# Boost_Converter.net
KiCad netlist of a schematic drawn in Altium Designer
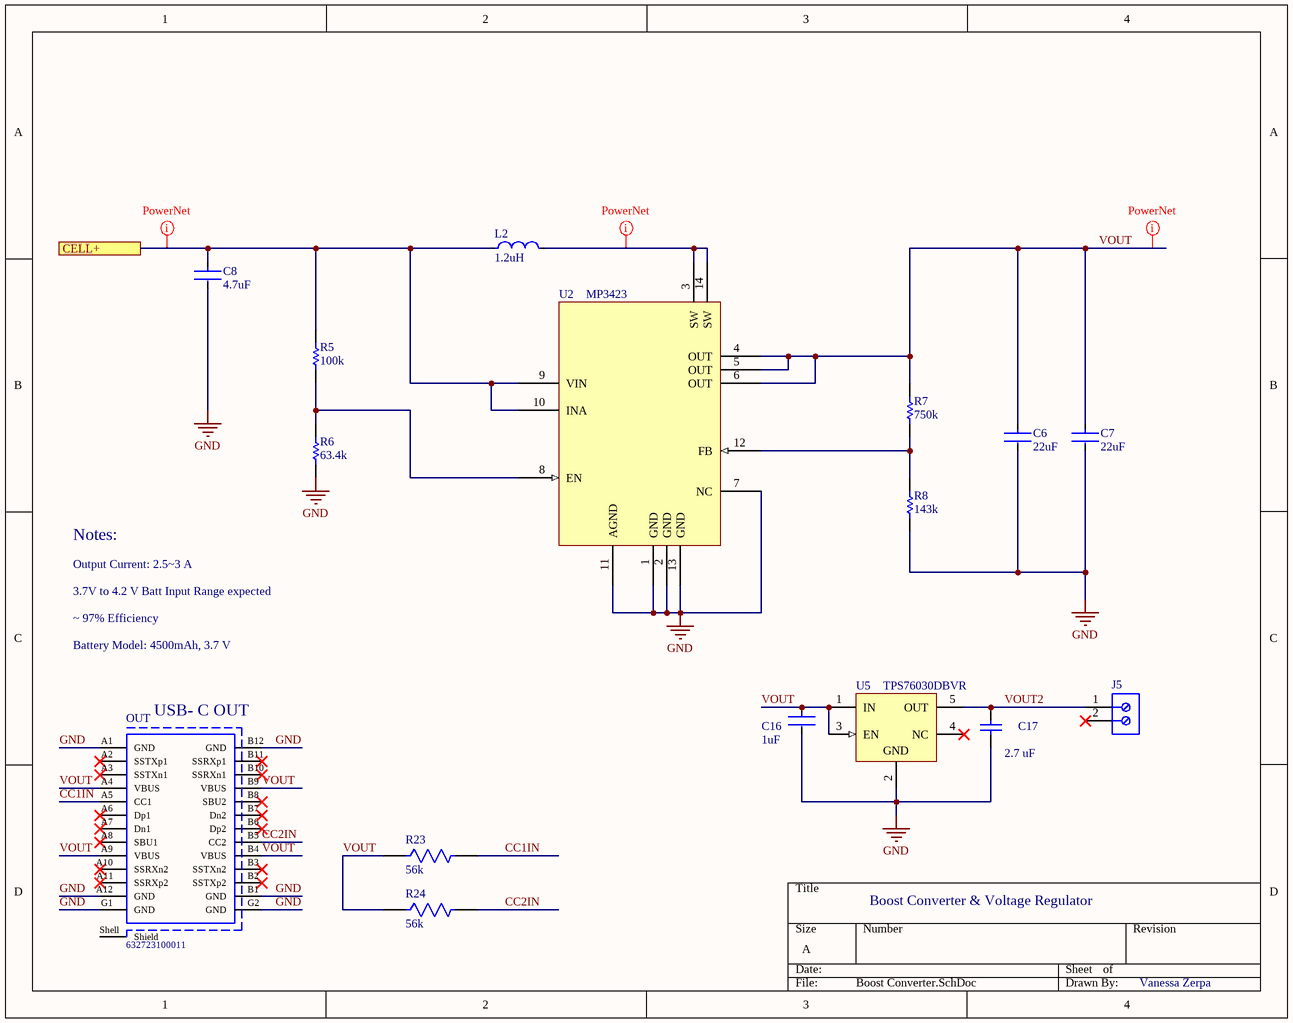
[diagram p0: Boost Converter.SchDoc]

(export (version "E")
  (design (tool "Eeschema 10.0.6"))
  (components
    (comp (ref "C6")
      (value "22uF")
      (footprint "FP-GRM21B-0_15-MFG")
      (description "Chip Multilayer Ceramic Capacitors for General Purpose, 0805, 22uF, X5R, 15%, 20%, 6.3V")
      (fields (field (name "VOLTAGE") "6.3V") (field (name "TOLERANCE") "20%"))
      (libsource (lib "Altium Content Vault") (part "b4654b650e69147ec39a6b967a45e02"))
    )
    (comp (ref "C7")
      (value "22uF")
      (footprint "FP-GRM21B-0_15-MFG")
      (description "Chip Multilayer Ceramic Capacitors for General Purpose, 0805, 22uF, X5R, 15%, 20%, 6.3V")
      (fields (field (name "VOLTAGE") "6.3V") (field (name "TOLERANCE") "20%"))
      (libsource (lib "Altium Content Vault") (part "b4654b650e69147ec39a6b967a45e02"))
    )
    (comp (ref "C8")
      (value "4.7uF")
      (footprint "FP-0805-L_2_01_0_2-W_1_25-MFG")
      (description "General Purpose Ceramic Capacitor, 0805, 4.7uF, 10%, X7R, 15%, 16V")
      (fields (field (name "VOLTAGE") "10V") (field (name "TOLERANCE") "10%"))
      (libsource (lib "Altium Content Vault") (part "02cd4be3c70576c341d710602a673aa"))
    )
    (comp (ref "C16")
      (value "1uF")
      (footprint "FP-CC0805-0_85-MFG")
      (description "CAP CER 1UF 10V X7R 0805")
      (fields
        (field (name "MANUFACTURER") "Yageo")
        (field (name "OCTOPART") "https://octopart.com/cc0805kkx7r6bb105-yageo-42522859")
      )
      (libsource (lib "Altium Content Vault") (part "11868f565c42a9108669ba33697ecf6"))
    )
    (comp (ref "C17")
      (value "2.7 uF")
      (footprint "CAPC2013X145X50LL20T25")
      (fields (field (name "PART NUMBER") "C0805C275K8PACTU") (field (name "MANUFACTURER") "Kemet"))
      (libsource (lib "Altium Content Vault") (part "CAP"))
    )
    (comp (ref "J5")
      (value "691101710002")
      (footprint "691101710002")
      (description "Series 101 - 5.00 mm Horizontal Entry Modular with Pressure Clamp WR-TBL, 2 pin")
      (fields (field (name "MANUFACTURER") "Wurth Elektronik") (field (name "PUBLISHER") "WurthElektronik"))
      (libsource (lib "Altium Content Vault") (part "WE-CN-1P-F-TB2"))
    )
    (comp (ref "L2")
      (value "1.2uH")
      (footprint "FP-LQW21HN_00-MFG")
      (description "Wire Wound Ferrite type RF Inuctor 1.2uH ±5% 100mA 3.12Ω 0805 (2012)")
      (fields (field (name "TOLERANCE") "5%"))
      (libsource (lib "Altium Content Vault") (part "725321dda6339637d4d059423bc1c3c"))
    )
    (comp (ref "OUT")
      (value "632723100011")
      (footprint "632723100011")
      (description "USB 3.1 Type C Receptacle WR-COM, Horizontal, SMT / THT")
      (fields (field (name "MANUFACTURER") "Wurth Elektronik") (field (name "PUBLISHER") "WurthElektronik"))
      (libsource (lib "Altium Content Vault") (part "WE-632723X00011"))
    )
    (comp (ref "R5")
      (value "100k")
      (footprint "RESC2013X60X35ML10T20")
      (description "Chip Resistor, 100 KOhm, +/- 1%, 0.125 W, -55 to 155 degC, 0805 (2012 Metric), RoHS, Tape and Reel")
      (fields (field (name "MANUFACTURER") "Yageo") (field (name "TOLERANCE") "1%"))
      (libsource (lib "Altium Content Vault") (part "RES-2"))
    )
    (comp (ref "R6")
      (value "63.4k")
      (footprint "RESC2013X50X30LL20T20")
      (fields (field (name "PART NUMBER") "CRCW080563K4FKEA") (field (name "MANUFACTURER") "Vishay Dale"))
      (libsource (lib "Altium Content Vault") (part "RES"))
    )
    (comp (ref "R7")
      (value "750k")
      (footprint "RESC2013X50X30LL20T20")
      (fields (field (name "MANUFACTURER") "Vishay Dale") (field (name "PART NUMBER") "CRCW0805750KFKEA"))
      (libsource (lib "Altium Content Vault") (part "RES"))
    )
    (comp (ref "R8")
      (value "143k")
      (footprint "RESC2013X70X40LL20T20")
      (fields (field (name "MANUFACTURER") "Panasonic") (field (name "PART NUMBER") "ERJ-6ENF1433V"))
      (libsource (lib "Altium Content Vault") (part "RES"))
    )
    (comp (ref "R23")
      (value "56k")
      (footprint "FP-CRCW0805-e3-IPC_B")
      (description "RES Thick Film, 56kΩ, 1%, 0.125W, 100ppm/°C, 0805")
      (fields (field (name "TOLERANCE") "1%"))
      (libsource (lib "Altium Content Vault") (part "1029c3af85768c4190bb7ad29bc67b5"))
    )
    (comp (ref "R24")
      (value "56k")
      (footprint "FP-CRCW0805-e3-IPC_B")
      (description "RES Thick Film, 56kΩ, 1%, 0.125W, 100ppm/°C, 0805")
      (fields (field (name "TOLERANCE") "1%"))
      (libsource (lib "Altium Content Vault") (part "1029c3af85768c4190bb7ad29bc67b5"))
    )
    (comp (ref "U2")
      (value "MP3423")
      (footprint "MP3422GGZ")
      (libsource (lib "BoostConverter") (part "MP3423"))
    )
    (comp (ref "U5")
      (value "TPS76030DBVR")
      (footprint "DBV0005A_L")
      (fields (field (name "MANUFACTURER") "Texas Instruments"))
      (libsource (lib "Altium Content Vault") (part "TI-TXX7XXXX-5"))
    )
  )
  (nets
    (net (code "1") (name "/CC1IN") (class "Default")
      (node (ref "OUT") (pin "A5") (pinfunction "CC1_A5") (pintype "passive"))
      (node (ref "R23") (pin "2") (pinfunction "2_2") (pintype "passive"))
    )
    (net (code "2") (name "/CC2IN") (class "Default")
      (node (ref "OUT") (pin "B5") (pinfunction "CC2_B5") (pintype "passive"))
      (node (ref "R24") (pin "2") (pinfunction "2_2") (pintype "passive"))
    )
    (net (code "3") (name "/CELL+") (class "Default")
      (node (ref "C8") (pin "1") (pinfunction "1_1") (pintype "passive"))
      (node (ref "L2") (pin "1") (pinfunction "1_1") (pintype "passive"))
      (node (ref "R5") (pin "2") (pinfunction "2_2") (pintype "passive"))
      (node (ref "U2") (pin "10") (pinfunction "INA_10") (pintype "passive"))
      (node (ref "U2") (pin "9") (pinfunction "VIN_9") (pintype "passive"))
    )
    (net (code "4") (name "/VOUT") (class "Default")
      (node (ref "C16") (pin "1") (pinfunction "1_1") (pintype "passive"))
      (node (ref "C6") (pin "1") (pinfunction "1_1") (pintype "passive"))
      (node (ref "C7") (pin "1") (pinfunction "1_1") (pintype "passive"))
      (node (ref "OUT") (pin "A4") (pinfunction "VBUS_A4") (pintype "passive"))
      (node (ref "OUT") (pin "A9") (pinfunction "VBUS_A9") (pintype "passive"))
      (node (ref "OUT") (pin "B4") (pinfunction "VBUS_B4") (pintype "passive"))
      (node (ref "OUT") (pin "B9") (pinfunction "VBUS_B9") (pintype "passive"))
      (node (ref "R23") (pin "1") (pinfunction "1_1") (pintype "passive"))
      (node (ref "R24") (pin "1") (pinfunction "1_1") (pintype "passive"))
      (node (ref "R7") (pin "2") (pinfunction "2_2") (pintype "passive"))
      (node (ref "U2") (pin "4") (pinfunction "OUT_4") (pintype "passive"))
      (node (ref "U2") (pin "5") (pinfunction "OUT_5") (pintype "passive"))
      (node (ref "U2") (pin "6") (pinfunction "OUT_6") (pintype "passive"))
      (node (ref "U5") (pin "1") (pinfunction "IN_1") (pintype "power_in"))
      (node (ref "U5") (pin "3") (pinfunction "EN_3") (pintype "input"))
    )
    (net (code "5") (name "/VOUT2") (class "Default")
      (node (ref "C17") (pin "1") (pinfunction "1_1") (pintype "passive"))
      (node (ref "J5") (pin "1") (pinfunction "1_1") (pintype "passive"))
      (node (ref "U5") (pin "5") (pinfunction "OUT_5") (pintype "power_in"))
    )
    (net (code "6") (name "GND") (class "Default")
      (node (ref "C16") (pin "2") (pinfunction "2_2") (pintype "passive"))
      (node (ref "C17") (pin "2") (pinfunction "2_2") (pintype "passive"))
      (node (ref "C6") (pin "2") (pinfunction "2_2") (pintype "passive"))
      (node (ref "C7") (pin "2") (pinfunction "2_2") (pintype "passive"))
      (node (ref "C8") (pin "2") (pinfunction "2_2") (pintype "passive"))
      (node (ref "OUT") (pin "A1") (pinfunction "GND_A1") (pintype "passive"))
      (node (ref "OUT") (pin "A12") (pinfunction "GND_A12") (pintype "passive"))
      (node (ref "OUT") (pin "B1") (pinfunction "GND_B1") (pintype "passive"))
      (node (ref "OUT") (pin "B12") (pinfunction "GND_B12") (pintype "passive"))
      (node (ref "OUT") (pin "G1") (pinfunction "GND_G1") (pintype "passive"))
      (node (ref "OUT") (pin "G2") (pinfunction "GND_G2") (pintype "passive"))
      (node (ref "R6") (pin "1") (pinfunction "1_1") (pintype "passive"))
      (node (ref "R8") (pin "1") (pinfunction "1_1") (pintype "passive"))
      (node (ref "U2") (pin "1") (pinfunction "GND_1") (pintype "passive"))
      (node (ref "U2") (pin "11") (pinfunction "AGND_11") (pintype "passive"))
      (node (ref "U2") (pin "13") (pinfunction "GND_13") (pintype "passive"))
      (node (ref "U2") (pin "2") (pinfunction "GND_2") (pintype "passive"))
      (node (ref "U2") (pin "7") (pinfunction "NC_7") (pintype "passive"))
      (node (ref "U5") (pin "2") (pinfunction "GND_2") (pintype "power_in"))
    )
    (net (code "7") (name "Net-(L2-Pad2)") (class "Default")
      (node (ref "L2") (pin "2") (pinfunction "2_2") (pintype "passive"))
      (node (ref "U2") (pin "14") (pinfunction "SW_14") (pintype "passive"))
      (node (ref "U2") (pin "3") (pinfunction "SW_3") (pintype "passive"))
    )
    (net (code "8") (name "Net-(U2-EN)") (class "Default")
      (node (ref "R5") (pin "1") (pinfunction "1_1") (pintype "passive"))
      (node (ref "R6") (pin "2") (pinfunction "2_2") (pintype "passive"))
      (node (ref "U2") (pin "8") (pinfunction "EN_8") (pintype "input"))
    )
    (net (code "9") (name "Net-(U2-FB)") (class "Default")
      (node (ref "R7") (pin "1") (pinfunction "1_1") (pintype "passive"))
      (node (ref "R8") (pin "2") (pinfunction "2_2") (pintype "passive"))
      (node (ref "U2") (pin "12") (pinfunction "FB_12") (pintype "input"))
    )
    (net (code "10") (name "unconnected-(J5-Pad2)") (class "Default")
      (node (ref "J5") (pin "2") (pinfunction "2_2") (pintype "passive+no_connect"))
    )
    (net (code "11") (name "unconnected-(OUT-Dn1-PadA7)") (class "Default")
      (node (ref "OUT") (pin "A7") (pinfunction "Dn1_A7") (pintype "passive+no_connect"))
    )
    (net (code "12") (name "unconnected-(OUT-Dn2-PadB7)") (class "Default")
      (node (ref "OUT") (pin "B7") (pinfunction "Dn2_B7") (pintype "passive+no_connect"))
    )
    (net (code "13") (name "unconnected-(OUT-Dp1-PadA6)") (class "Default")
      (node (ref "OUT") (pin "A6") (pinfunction "Dp1_A6") (pintype "passive+no_connect"))
    )
    (net (code "14") (name "unconnected-(OUT-Dp2-PadB6)") (class "Default")
      (node (ref "OUT") (pin "B6") (pinfunction "Dp2_B6") (pintype "passive+no_connect"))
    )
    (net (code "15") (name "unconnected-(OUT-SBU1-PadA8)") (class "Default")
      (node (ref "OUT") (pin "A8") (pinfunction "SBU1_A8") (pintype "passive+no_connect"))
    )
    (net (code "16") (name "unconnected-(OUT-SBU2-PadB8)") (class "Default")
      (node (ref "OUT") (pin "B8") (pinfunction "SBU2_B8") (pintype "passive+no_connect"))
    )
    (net (code "17") (name "unconnected-(OUT-SSRXn1-PadB10)") (class "Default")
      (node (ref "OUT") (pin "B10") (pinfunction "SSRXn1_B10") (pintype "passive+no_connect"))
    )
    (net (code "18") (name "unconnected-(OUT-SSRXn2-PadA10)") (class "Default")
      (node (ref "OUT") (pin "A10") (pinfunction "SSRXn2_A10") (pintype "passive+no_connect"))
    )
    (net (code "19") (name "unconnected-(OUT-SSRXp1-PadB11)") (class "Default")
      (node (ref "OUT") (pin "B11") (pinfunction "SSRXp1_B11") (pintype "passive+no_connect"))
    )
    (net (code "20") (name "unconnected-(OUT-SSRXp2-PadA11)") (class "Default")
      (node (ref "OUT") (pin "A11") (pinfunction "SSRXp2_A11") (pintype "passive+no_connect"))
    )
    (net (code "21") (name "unconnected-(OUT-SSTXn1-PadA3)") (class "Default")
      (node (ref "OUT") (pin "A3") (pinfunction "SSTXn1_A3") (pintype "passive+no_connect"))
    )
    (net (code "22") (name "unconnected-(OUT-SSTXn2-PadB3)") (class "Default")
      (node (ref "OUT") (pin "B3") (pinfunction "SSTXn2_B3") (pintype "passive+no_connect"))
    )
    (net (code "23") (name "unconnected-(OUT-SSTXp1-PadA2)") (class "Default")
      (node (ref "OUT") (pin "A2") (pinfunction "SSTXp1_A2") (pintype "passive+no_connect"))
    )
    (net (code "24") (name "unconnected-(OUT-SSTXp2-PadB2)") (class "Default")
      (node (ref "OUT") (pin "B2") (pinfunction "SSTXp2_B2") (pintype "passive+no_connect"))
    )
    (net (code "25") (name "unconnected-(OUT-Shield-PadShell)") (class "Default")
      (node (ref "OUT") (pin "Shell") (pinfunction "Shield_Shell") (pintype "passive"))
    )
    (net (code "26") (name "unconnected-(U5-NC-Pad4)") (class "Default")
      (node (ref "U5") (pin "4") (pinfunction "NC_4") (pintype "passive+no_connect"))
    )
  )
)
